# DM3390_IMU.net
KiCad netlist of a schematic drawn in Altium Designer
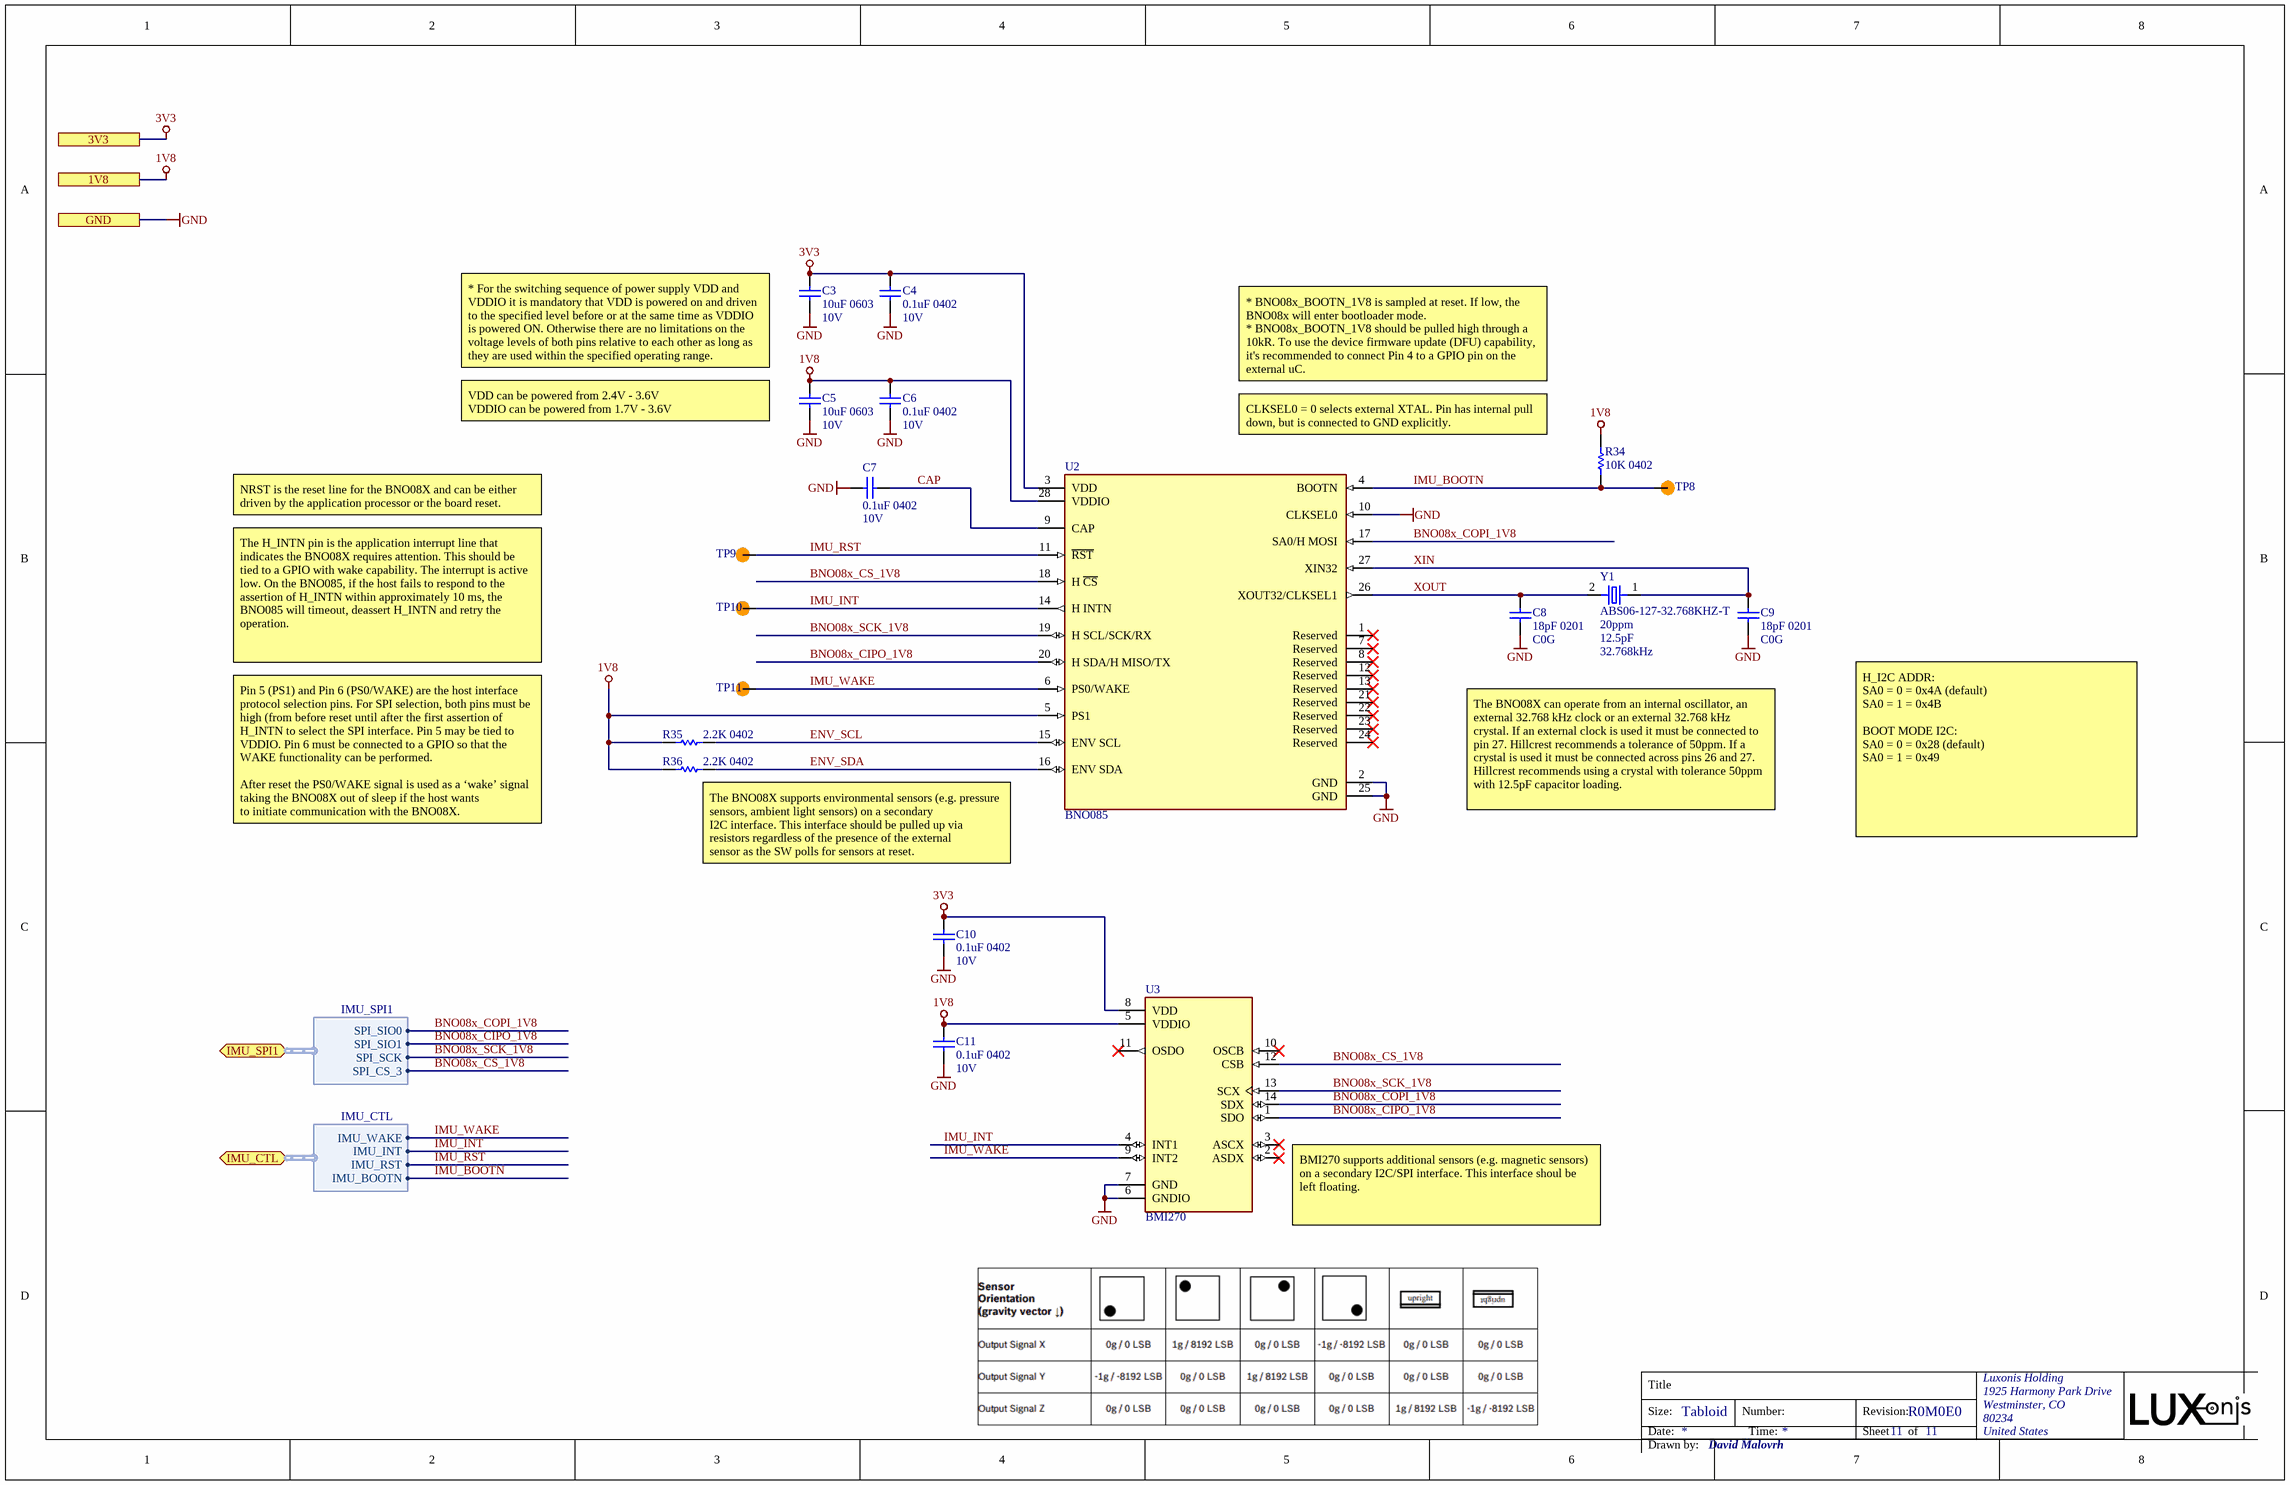
[diagram p0: DM3390_IMU.SchDoc]

(export (version "E")
  (design (tool "Eeschema 10.0.6"))
  (components
    (comp (ref "C3")
      (value "10uF 0603")
      (footprint "CAP_Altium_Vault_Generic:CAPC0603(1608)100_L")
      (description "CAP CER 10UF 10V X5R 0603 20%")
      (fields (field (name "TOLERANCE") "20%") (field (name "VOLTAGE RATING") "10V"))
      (libsource (lib "LuxonisMaster") (part "GRM188R61A106ME69D"))
    )
    (comp (ref "C4")
      (value "0.1uF 0402")
      (footprint "CAP_Altium_Vault_Generic:CAPC0402(1005)70_L")
      (description "CAP CER 0.1UF 10V X7R 0402 5%")
      (fields (field (name "TOLERANCE") "5%") (field (name "VOLTAGE RATING") "10V"))
      (libsource (lib "LuxonisMaster") (part "GRM155R71A104JA01D"))
    )
    (comp (ref "C5")
      (value "10uF 0603")
      (footprint "CAP_Altium_Vault_Generic:CAPC0603(1608)100_L")
      (description "CAP CER 10UF 10V X5R 0603 20%")
      (fields (field (name "TOLERANCE") "20%") (field (name "VOLTAGE RATING") "10V"))
      (libsource (lib "LuxonisMaster") (part "GRM188R61A106ME69D"))
    )
    (comp (ref "C6")
      (value "0.1uF 0402")
      (footprint "CAP_Altium_Vault_Generic:CAPC0402(1005)70_L")
      (description "CAP CER 0.1UF 10V X7R 0402 5%")
      (fields (field (name "TOLERANCE") "5%") (field (name "VOLTAGE RATING") "10V"))
      (libsource (lib "LuxonisMaster") (part "GRM155R71A104JA01D"))
    )
    (comp (ref "C7")
      (value "0.1uF 0402")
      (footprint "CAP_Altium_Vault_Generic:CAPC0402(1005)70_L")
      (description "CAP CER 0.1UF 10V X7R 0402 5%")
      (fields (field (name "TOLERANCE") "5%") (field (name "VOLTAGE RATING") "10V"))
      (libsource (lib "LuxonisMaster") (part "GRM155R71A104JA01D"))
    )
    (comp (ref "C8")
      (value "18pF 0201")
      (footprint "CAP_Altium_Vault_Generic:CAPC0201(0603)33_L")
      (description "Cap Ceramic 18pF 25V C0G 1% Pad SMD 0201 125C T/R")
      (fields (field (name "TOLERANCE") "1%") (field (name "DIELECTRIC") "C0G"))
      (libsource (lib "BW1092_R0M0E0") (part "GRM0335C1E180FA01D"))
    )
    (comp (ref "C9")
      (value "18pF 0201")
      (footprint "CAP_Altium_Vault_Generic:CAPC0201(0603)33_L")
      (description "Cap Ceramic 18pF 25V C0G 1% Pad SMD 0201 125C T/R")
      (fields (field (name "TOLERANCE") "1%") (field (name "DIELECTRIC") "C0G"))
      (libsource (lib "BW1092_R0M0E0") (part "GRM0335C1E180FA01D"))
    )
    (comp (ref "C10")
      (value "0.1uF 0402")
      (footprint "CAP_Altium_Vault_Generic:CAPC0402(1005)70_L")
      (description "CAP CER 0.1UF 10V X7R 0402 5%")
      (fields (field (name "TOLERANCE") "5%") (field (name "VOLTAGE RATING") "10V"))
      (libsource (lib "LuxonisMaster") (part "GRM155R71A104JA01D"))
    )
    (comp (ref "C11")
      (value "0.1uF 0402")
      (footprint "CAP_Altium_Vault_Generic:CAPC0402(1005)70_L")
      (description "CAP CER 0.1UF 10V X7R 0402 5%")
      (fields (field (name "TOLERANCE") "5%") (field (name "VOLTAGE RATING") "10V"))
      (libsource (lib "LuxonisMaster") (part "GRM155R71A104JA01D"))
    )
    (comp (ref "R34")
      (value "10K 0402")
      (footprint "RES_Altium_Vault_Generic:RESC0402(1005)_L")
      (fields (field (name "TOLERANCE") "1%"))
      (libsource (lib "LuxonisMaster") (part "RC0402FR-1310KL"))
    )
    (comp (ref "R35")
      (value "2.2K 0402")
      (footprint "RES_Altium_Vault_Generic:RESC0402(1005)_L")
      (description "RES SMD 2.2K OHM 1% 1/16W 0402")
      (fields (field (name "TOLERANCE") "1%"))
      (libsource (lib "LuxonisMaster") (part "RC0402FR-072K2L"))
    )
    (comp (ref "R36")
      (value "2.2K 0402")
      (footprint "RES_Altium_Vault_Generic:RESC0402(1005)_L")
      (description "RES SMD 2.2K OHM 1% 1/16W 0402")
      (fields (field (name "TOLERANCE") "1%"))
      (libsource (lib "LuxonisMaster") (part "RC0402FR-072K2L"))
    )
    (comp (ref "TP8")
      (value "TP100_200_NS")
      (footprint "LuxonisMaster:TP100_200_NS")
      (libsource (lib "LuxonisMaster") (part "TEST_POINT"))
    )
    (comp (ref "TP9")
      (value "TP100_200_NS")
      (footprint "LuxonisMaster:TP100_200_NS")
      (libsource (lib "LuxonisMaster") (part "TEST_POINT"))
    )
    (comp (ref "TP10")
      (value "TP100_200_NS")
      (footprint "LuxonisMaster:TP100_200_NS")
      (libsource (lib "LuxonisMaster") (part "TEST_POINT"))
    )
    (comp (ref "TP11")
      (value "TP100_200_NS")
      (footprint "LuxonisMaster:TP100_200_NS")
      (libsource (lib "LuxonisMaster") (part "TEST_POINT"))
    )
    (comp (ref "U2")
      (value "BNO085")
      (footprint "BNO085")
      (description "IMU ACCEL/GYRO/MAG I2C 32BIT")
      (libsource (lib "DM1092_R0M0E0") (part "BNO085"))
    )
    (comp (ref "U3")
      (value "BMI270")
      (footprint "XDCR_BMI270")
      (description "Accelerometer, Gyroscope, 6 Axis Sensor IÂ²C, SPI Output")
      (libsource (lib "DM1098LUXD-LITE") (part "BMI270"))
    )
    (comp (ref "Y1")
      (value "ABS06-127-32.768KHZ-T")
      (footprint "ABS06-127-32.768KHZ-T")
      (description "CRYSTAL 32.768kHz ±20ppm Crystal 12.5pF 90 kOhms 2-SMD, No Lead")
      (fields
        (field (name "FREQUENCY TOLERANCE") "20ppm")
        (field (name "LOAD CAPACITANCE") "12.5pF")
        (field (name "FREQUENCY") "32.768kHz")
      )
      (libsource (lib "DM1092_R0M0E0") (part "ABS06-127-32.768KHZ-T"))
    )
  )
  (nets
    (net (code "3") (name "/BNO08x_CIPO_1V8") (class "Default")
      (node (ref "U2") (pin "20") (pinfunction "H_SDA/H_MISO/TX_20") (pintype "bidirectional"))
      (node (ref "U3") (pin "1") (pinfunction "SDO_1") (pintype "bidirectional"))
    )
    (net (code "4") (name "/BNO08x_COPI_1V8") (class "Default")
      (node (ref "U2") (pin "17") (pinfunction "SA0/H_MOSI_17") (pintype "input"))
      (node (ref "U3") (pin "14") (pinfunction "SDX_14") (pintype "bidirectional"))
    )
    (net (code "5") (name "/BNO08x_CS_1V8") (class "Default")
      (node (ref "U2") (pin "18") (pinfunction "H_~{CS}_18") (pintype "input"))
      (node (ref "U3") (pin "12") (pinfunction "CSB_12") (pintype "input"))
    )
    (net (code "6") (name "/BNO08x_SCK_1V8") (class "Default")
      (node (ref "U2") (pin "19") (pinfunction "H_SCL/SCK/RX_19") (pintype "bidirectional"))
      (node (ref "U3") (pin "13") (pinfunction "SCX_13") (pintype "input"))
    )
    (net (code "7") (name "/CAP") (class "Default")
      (node (ref "C7") (pin "1") (pinfunction "1_1") (pintype "passive"))
      (node (ref "U2") (pin "9") (pinfunction "CAP_9") (pintype "passive"))
    )
    (net (code "8") (name "/ENV_SCL") (class "Default")
      (node (ref "R35") (pin "2") (pinfunction "2_2") (pintype "passive"))
      (node (ref "U2") (pin "15") (pinfunction "ENV_SCL_15") (pintype "bidirectional"))
    )
    (net (code "9") (name "/ENV_SDA") (class "Default")
      (node (ref "R36") (pin "2") (pinfunction "2_2") (pintype "passive"))
      (node (ref "U2") (pin "16") (pinfunction "ENV_SDA_16") (pintype "bidirectional"))
    )
    (net (code "10") (name "/IMU_BOOTN") (class "Default")
      (node (ref "R34") (pin "1") (pinfunction "1_1") (pintype "passive"))
      (node (ref "TP8") (pin "1") (pintype "passive"))
      (node (ref "U2") (pin "4") (pinfunction "BOOTN_4") (pintype "input"))
    )
    (net (code "11") (name "/IMU_INT") (class "Default")
      (node (ref "TP10") (pin "1") (pintype "passive"))
      (node (ref "U2") (pin "14") (pinfunction "H_INTN_14") (pintype "output"))
      (node (ref "U3") (pin "4") (pinfunction "INT1_4") (pintype "bidirectional"))
    )
    (net (code "12") (name "/IMU_RST") (class "Default")
      (node (ref "TP9") (pin "1") (pintype "passive"))
      (node (ref "U2") (pin "11") (pinfunction "~{RST}_11") (pintype "input"))
    )
    (net (code "13") (name "/IMU_WAKE") (class "Default")
      (node (ref "TP11") (pin "1") (pintype "passive"))
      (node (ref "U2") (pin "6") (pinfunction "PS0/WAKE_6") (pintype "input"))
      (node (ref "U3") (pin "9") (pinfunction "INT2_9") (pintype "bidirectional"))
    )
    (net (code "14") (name "/XIN") (class "Default")
      (node (ref "C9") (pin "2") (pinfunction "2_2") (pintype "passive"))
      (node (ref "U2") (pin "27") (pinfunction "XIN32_27") (pintype "input"))
      (node (ref "Y1") (pin "1") (pinfunction "1_1") (pintype "passive"))
    )
    (net (code "15") (name "/XOUT") (class "Default")
      (node (ref "C8") (pin "2") (pinfunction "2_2") (pintype "passive"))
      (node (ref "U2") (pin "26") (pinfunction "XOUT32/CLKSEL1_26") (pintype "output"))
      (node (ref "Y1") (pin "2") (pinfunction "2_2") (pintype "passive"))
    )
    (net (code "18") (name "1V8") (class "Default")
      (node (ref "C11") (pin "2") (pinfunction "2_2") (pintype "passive"))
      (node (ref "C5") (pin "2") (pinfunction "2_2") (pintype "passive"))
      (node (ref "C6") (pin "2") (pinfunction "2_2") (pintype "passive"))
      (node (ref "R34") (pin "2") (pinfunction "2_2") (pintype "passive"))
      (node (ref "R35") (pin "1") (pinfunction "1_1") (pintype "passive"))
      (node (ref "R36") (pin "1") (pinfunction "1_1") (pintype "passive"))
      (node (ref "U2") (pin "28") (pinfunction "VDDIO_28") (pintype "power_in"))
      (node (ref "U2") (pin "5") (pinfunction "PS1_5") (pintype "input"))
      (node (ref "U3") (pin "5") (pinfunction "VDDIO_5") (pintype "power_in"))
    )
    (net (code "19") (name "3V3") (class "Default")
      (node (ref "C10") (pin "2") (pinfunction "2_2") (pintype "passive"))
      (node (ref "C3") (pin "2") (pinfunction "2_2") (pintype "passive"))
      (node (ref "C4") (pin "2") (pinfunction "2_2") (pintype "passive"))
      (node (ref "U2") (pin "3") (pinfunction "VDD_3") (pintype "power_in"))
      (node (ref "U3") (pin "8") (pinfunction "VDD_8") (pintype "power_in"))
    )
    (net (code "20") (name "GND") (class "Default")
      (node (ref "C10") (pin "1") (pinfunction "1_1") (pintype "passive"))
      (node (ref "C11") (pin "1") (pinfunction "1_1") (pintype "passive"))
      (node (ref "C3") (pin "1") (pinfunction "1_1") (pintype "passive"))
      (node (ref "C4") (pin "1") (pinfunction "1_1") (pintype "passive"))
      (node (ref "C5") (pin "1") (pinfunction "1_1") (pintype "passive"))
      (node (ref "C6") (pin "1") (pinfunction "1_1") (pintype "passive"))
      (node (ref "C7") (pin "2") (pinfunction "2_2") (pintype "passive"))
      (node (ref "C8") (pin "1") (pinfunction "1_1") (pintype "passive"))
      (node (ref "C9") (pin "1") (pinfunction "1_1") (pintype "passive"))
      (node (ref "U2") (pin "10") (pinfunction "CLKSEL0_10") (pintype "input"))
      (node (ref "U2") (pin "2") (pinfunction "GND_2") (pintype "power_in"))
      (node (ref "U2") (pin "25") (pinfunction "GND_25") (pintype "power_in"))
      (node (ref "U3") (pin "6") (pinfunction "GNDIO_6") (pintype "power_in"))
      (node (ref "U3") (pin "7") (pinfunction "GND_7") (pintype "power_in"))
    )
    (net (code "21") (name "unconnected-(U2-Reserved-Pad1)") (class "Default")
      (node (ref "U2") (pin "1") (pinfunction "Reserved_1") (pintype "passive+no_connect"))
    )
    (net (code "22") (name "unconnected-(U2-Reserved-Pad7)") (class "Default")
      (node (ref "U2") (pin "7") (pinfunction "Reserved_7") (pintype "passive+no_connect"))
    )
    (net (code "23") (name "unconnected-(U2-Reserved-Pad8)") (class "Default")
      (node (ref "U2") (pin "8") (pinfunction "Reserved_8") (pintype "passive+no_connect"))
    )
    (net (code "24") (name "unconnected-(U2-Reserved-Pad12)") (class "Default")
      (node (ref "U2") (pin "12") (pinfunction "Reserved_12") (pintype "passive+no_connect"))
    )
    (net (code "25") (name "unconnected-(U2-Reserved-Pad13)") (class "Default")
      (node (ref "U2") (pin "13") (pinfunction "Reserved_13") (pintype "passive+no_connect"))
    )
    (net (code "26") (name "unconnected-(U2-Reserved-Pad21)") (class "Default")
      (node (ref "U2") (pin "21") (pinfunction "Reserved_21") (pintype "passive+no_connect"))
    )
    (net (code "27") (name "unconnected-(U2-Reserved-Pad22)") (class "Default")
      (node (ref "U2") (pin "22") (pinfunction "Reserved_22") (pintype "passive+no_connect"))
    )
    (net (code "28") (name "unconnected-(U2-Reserved-Pad23)") (class "Default")
      (node (ref "U2") (pin "23") (pinfunction "Reserved_23") (pintype "passive+no_connect"))
    )
    (net (code "29") (name "unconnected-(U2-Reserved-Pad24)") (class "Default")
      (node (ref "U2") (pin "24") (pinfunction "Reserved_24") (pintype "passive+no_connect"))
    )
    (net (code "30") (name "unconnected-(U3-ASCX-Pad3)") (class "Default")
      (node (ref "U3") (pin "3") (pinfunction "ASCX_3") (pintype "bidirectional+no_connect"))
    )
    (net (code "31") (name "unconnected-(U3-ASDX-Pad2)") (class "Default")
      (node (ref "U3") (pin "2") (pinfunction "ASDX_2") (pintype "bidirectional+no_connect"))
    )
    (net (code "32") (name "unconnected-(U3-OSCB-Pad10)") (class "Default")
      (node (ref "U3") (pin "10") (pinfunction "OSCB_10") (pintype "input+no_connect"))
    )
    (net (code "33") (name "unconnected-(U3-OSDO-Pad11)") (class "Default")
      (node (ref "U3") (pin "11") (pinfunction "OSDO_11") (pintype "output+no_connect"))
    )
  )
)
